# main.net
KiCad netlist of a schematic drawn in Altium Designer
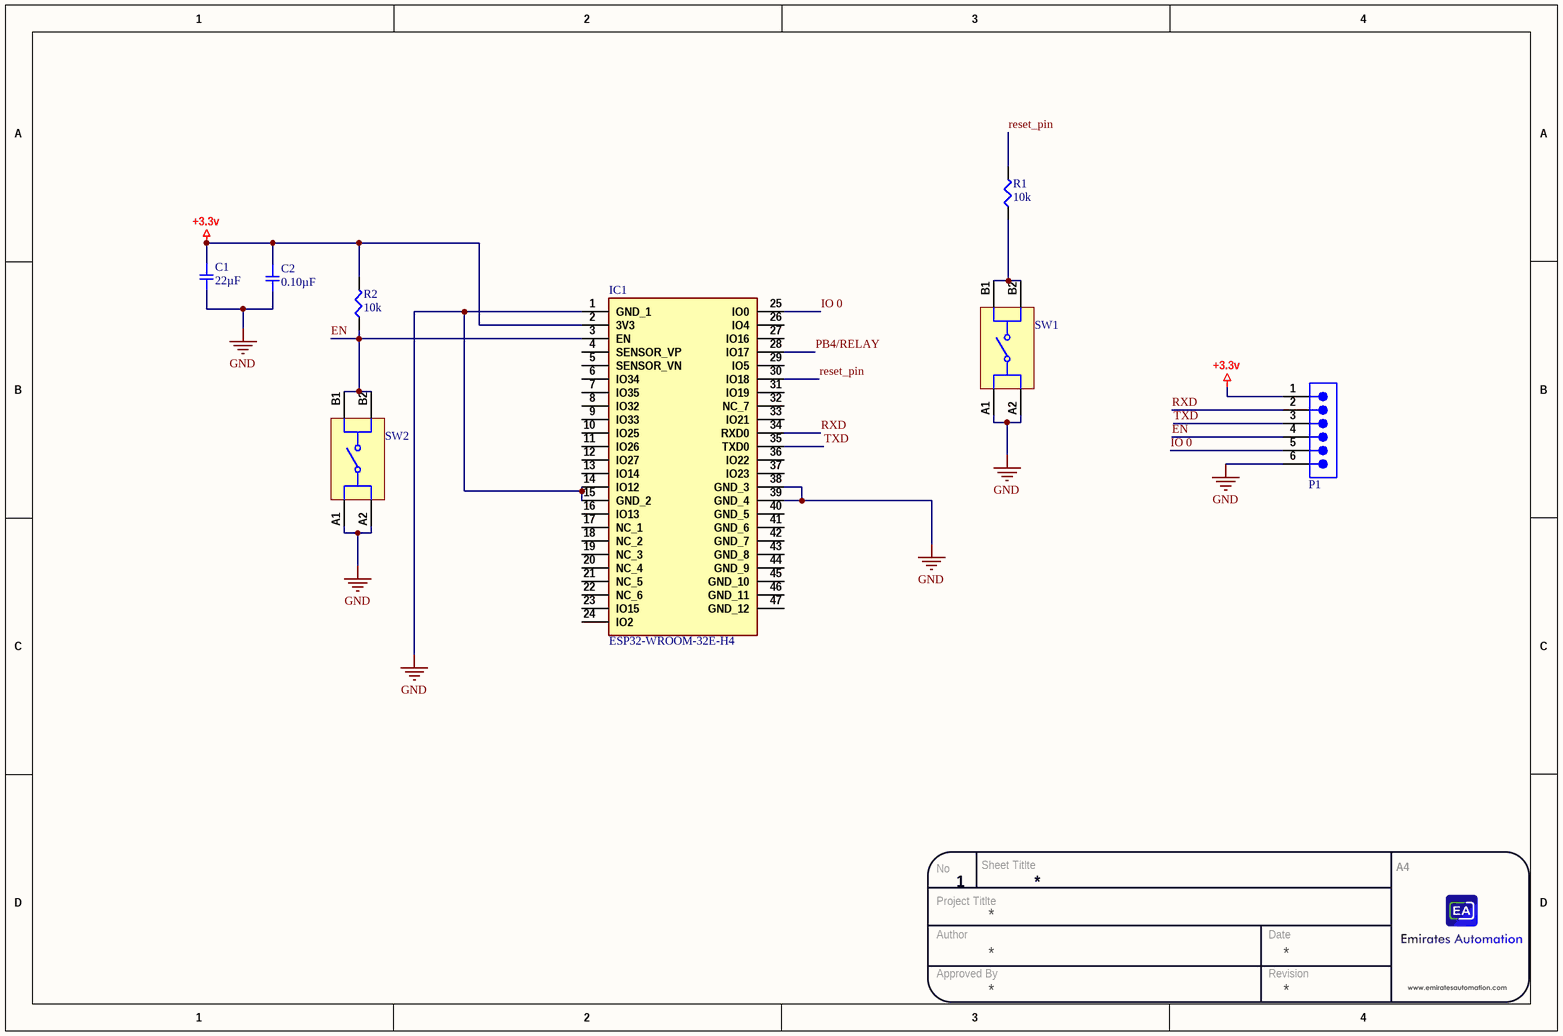
[diagram p0: main.SchDoc]

(export (version "E")
  (design (tool "Eeschema 10.0.6"))
  (components
    (comp (ref "C1")
      (value "22µF")
      (footprint "SMD-0603C")
      (description "CAP CER 22UF 10V X5R 0603")
      (fields
        (field (name "DIGI-KEY PART NUMBER") "490-10476-1-ND")
        (field (name "PART NUMBER") "GRM188R61A226ME15D")
      )
      (libsource (lib "capacitor_murata_0603") (part "GRM188R61A226ME15D"))
    )
    (comp (ref "C2")
      (value "0.10µF")
      (footprint "SMD-0603C")
      (description "CAP CER 0.1UF 16V X7R 0603")
      (fields
        (field (name "DIGI-KEY PART NUMBER") "490-5796-1-ND")
        (field (name "PART NUMBER") "GCJ188R71C104KA01D")
      )
      (libsource (lib "capacitor_murata_0603") (part "GCJ188R71C104KA01D"))
    )
    (comp (ref "IC1")
      (value "ESP32-WROOM-32E-H4")
      (footprint "SamacSys:ESP32WROOM32UEM113EH2800UH3Q0")
      (description "Integrated Circuit")
      (fields (field (name "MOUSER PART NUMBER") "356-ESP32WRM320EH3PS"))
      (libsource (lib "SamacSys") (part "ESP32-WROOM-32E-H4"))
    )
    (comp (ref "P1")
      (value "61300611121")
      (footprint "61300611121")
      (description "WR-PHD Pin Header, THT, Vertical, pitch 2.54mm, 1 Row, 6P")
      (fields (field (name "MANUFACTURER") "Wurth Elektronik"))
      (libsource (lib "Wurth_pin_header") (part "61300611121"))
    )
    (comp (ref "R1")
      (value "10k")
      (footprint "SMD-0603-RES")
      (description "RES SMD 10K OHM 1% 1/10W 0603")
      (fields
        (field (name "PART NUMBER") "ERJ-3EKF1002V")
        (field (name "DIGI-KEY PART NUMBER") "P10.0KHCT-ND")
      )
      (libsource (lib "Panasonic_ERJ_0603") (part "ERJ-3EKF1002V"))
    )
    (comp (ref "R2")
      (value "10k")
      (footprint "SMD-0603-RES")
      (description "RES SMD 10K OHM 1% 1/10W 0603")
      (fields
        (field (name "PART NUMBER") "ERJ-3EKF1002V")
        (field (name "DIGI-KEY PART NUMBER") "P10.0KHCT-ND")
      )
      (libsource (lib "Panasonic_ERJ_0603") (part "ERJ-3EKF1002V"))
    )
    (comp (ref "SW1")
      (value "430476085716")
      (footprint "430476085716")
      (description "WS-TATV THT Washable Tact Switch 12x12mm, 160g, SPST-NO, 12V, 50mA")
      (fields (field (name "MANUFACTURER") "Wurth Elektronik"))
      (libsource (lib "Wurth TATV THT Tact Switch 6x6 mm ") (part "430476085716"))
    )
    (comp (ref "SW2")
      (value "430476085716")
      (footprint "430476085716")
      (description "WS-TATV THT Washable Tact Switch 12x12mm, 160g, SPST-NO, 12V, 50mA")
      (fields (field (name "MANUFACTURER") "Wurth Elektronik"))
      (libsource (lib "Wurth TATV THT Tact Switch 6x6 mm ") (part "430476085716"))
    )
  )
  (nets
    (net (code "1") (name "+3.3v") (class "Default")
      (node (ref "C1") (pin "1") (pinfunction "1_1") (pintype "passive"))
      (node (ref "C2") (pin "1") (pinfunction "1_1") (pintype "passive"))
      (node (ref "IC1") (pin "2") (pinfunction "3V3_2") (pintype "passive"))
      (node (ref "P1") (pin "1") (pinfunction "1_1") (pintype "passive"))
      (node (ref "R2") (pin "2") (pinfunction "2_2") (pintype "passive"))
    )
    (net (code "2") (name "/EN") (class "Default")
      (node (ref "IC1") (pin "3") (pinfunction "EN_3") (pintype "passive"))
      (node (ref "P1") (pin "4") (pinfunction "4_4") (pintype "passive"))
      (node (ref "R2") (pin "1") (pinfunction "1_1") (pintype "passive"))
      (node (ref "SW2") (pin "B1") (pinfunction "B1_B1") (pintype "passive"))
      (node (ref "SW2") (pin "B2") (pinfunction "B2_B2") (pintype "passive"))
    )
    (net (code "3") (name "/IO 0") (class "Default")
      (node (ref "IC1") (pin "25") (pinfunction "IO0_25") (pintype "passive"))
      (node (ref "P1") (pin "5") (pinfunction "5_5") (pintype "passive"))
    )
    (net (code "4") (name "/PB4{slash}RELAY") (class "Default")
      (node (ref "IC1") (pin "28") (pinfunction "IO17_28") (pintype "passive"))
    )
    (net (code "5") (name "/RXD") (class "Default")
      (node (ref "IC1") (pin "34") (pinfunction "RXD0_34") (pintype "passive"))
      (node (ref "P1") (pin "2") (pinfunction "2_2") (pintype "passive"))
    )
    (net (code "6") (name "/TXD") (class "Default")
      (node (ref "IC1") (pin "35") (pinfunction "TXD0_35") (pintype "passive"))
      (node (ref "P1") (pin "3") (pinfunction "3_3") (pintype "passive"))
    )
    (net (code "7") (name "/reset_pin") (class "Default")
      (node (ref "IC1") (pin "30") (pinfunction "IO18_30") (pintype "passive"))
      (node (ref "R1") (pin "2") (pinfunction "2_2") (pintype "passive"))
    )
    (net (code "8") (name "GND") (class "Default")
      (node (ref "C1") (pin "2") (pinfunction "2_2") (pintype "passive"))
      (node (ref "C2") (pin "2") (pinfunction "2_2") (pintype "passive"))
      (node (ref "IC1") (pin "1") (pinfunction "GND_1_1") (pintype "passive"))
      (node (ref "IC1") (pin "14") (pinfunction "IO12_14") (pintype "passive"))
      (node (ref "IC1") (pin "15") (pinfunction "GND_2_15") (pintype "passive"))
      (node (ref "IC1") (pin "38") (pinfunction "GND_3_38") (pintype "passive"))
      (node (ref "IC1") (pin "39") (pinfunction "GND_4_39") (pintype "passive"))
      (node (ref "P1") (pin "6") (pinfunction "6_6") (pintype "passive"))
      (node (ref "SW1") (pin "A1") (pinfunction "A1_A1") (pintype "passive"))
      (node (ref "SW1") (pin "A2") (pinfunction "A2_A2") (pintype "passive"))
      (node (ref "SW2") (pin "A1") (pinfunction "A1_A1") (pintype "passive"))
      (node (ref "SW2") (pin "A2") (pinfunction "A2_A2") (pintype "passive"))
    )
    (net (code "9") (name "Net-(R1-Pad1)") (class "Default")
      (node (ref "R1") (pin "1") (pinfunction "1_1") (pintype "passive"))
      (node (ref "SW1") (pin "B1") (pinfunction "B1_B1") (pintype "passive"))
      (node (ref "SW1") (pin "B2") (pinfunction "B2_B2") (pintype "passive"))
    )
    (net (code "10") (name "unconnected-(IC1-GND_5-Pad40)") (class "Default")
      (node (ref "IC1") (pin "40") (pinfunction "GND_5_40") (pintype "passive"))
    )
    (net (code "11") (name "unconnected-(IC1-GND_6-Pad41)") (class "Default")
      (node (ref "IC1") (pin "41") (pinfunction "GND_6_41") (pintype "passive"))
    )
    (net (code "12") (name "unconnected-(IC1-GND_7-Pad42)") (class "Default")
      (node (ref "IC1") (pin "42") (pinfunction "GND_7_42") (pintype "passive"))
    )
    (net (code "13") (name "unconnected-(IC1-GND_8-Pad43)") (class "Default")
      (node (ref "IC1") (pin "43") (pinfunction "GND_8_43") (pintype "passive"))
    )
    (net (code "14") (name "unconnected-(IC1-GND_9-Pad44)") (class "Default")
      (node (ref "IC1") (pin "44") (pinfunction "GND_9_44") (pintype "passive"))
    )
    (net (code "15") (name "unconnected-(IC1-GND_10-Pad45)") (class "Default")
      (node (ref "IC1") (pin "45") (pinfunction "GND_10_45") (pintype "passive"))
    )
    (net (code "16") (name "unconnected-(IC1-GND_11-Pad46)") (class "Default")
      (node (ref "IC1") (pin "46") (pinfunction "GND_11_46") (pintype "passive"))
    )
    (net (code "17") (name "unconnected-(IC1-GND_12-Pad47)") (class "Default")
      (node (ref "IC1") (pin "47") (pinfunction "GND_12_47") (pintype "passive"))
    )
    (net (code "18") (name "unconnected-(IC1-IO2-Pad24)") (class "Default")
      (node (ref "IC1") (pin "24") (pinfunction "IO2_24") (pintype "passive"))
    )
    (net (code "19") (name "unconnected-(IC1-IO4-Pad26)") (class "Default")
      (node (ref "IC1") (pin "26") (pinfunction "IO4_26") (pintype "passive"))
    )
    (net (code "20") (name "unconnected-(IC1-IO5-Pad29)") (class "Default")
      (node (ref "IC1") (pin "29") (pinfunction "IO5_29") (pintype "passive"))
    )
    (net (code "21") (name "unconnected-(IC1-IO13-Pad16)") (class "Default")
      (node (ref "IC1") (pin "16") (pinfunction "IO13_16") (pintype "passive"))
    )
    (net (code "22") (name "unconnected-(IC1-IO14-Pad13)") (class "Default")
      (node (ref "IC1") (pin "13") (pinfunction "IO14_13") (pintype "passive"))
    )
    (net (code "23") (name "unconnected-(IC1-IO15-Pad23)") (class "Default")
      (node (ref "IC1") (pin "23") (pinfunction "IO15_23") (pintype "passive"))
    )
    (net (code "24") (name "unconnected-(IC1-IO16-Pad27)") (class "Default")
      (node (ref "IC1") (pin "27") (pinfunction "IO16_27") (pintype "passive"))
    )
    (net (code "25") (name "unconnected-(IC1-IO19-Pad31)") (class "Default")
      (node (ref "IC1") (pin "31") (pinfunction "IO19_31") (pintype "passive"))
    )
    (net (code "26") (name "unconnected-(IC1-IO21-Pad33)") (class "Default")
      (node (ref "IC1") (pin "33") (pinfunction "IO21_33") (pintype "passive"))
    )
    (net (code "27") (name "unconnected-(IC1-IO22-Pad36)") (class "Default")
      (node (ref "IC1") (pin "36") (pinfunction "IO22_36") (pintype "passive"))
    )
    (net (code "28") (name "unconnected-(IC1-IO23-Pad37)") (class "Default")
      (node (ref "IC1") (pin "37") (pinfunction "IO23_37") (pintype "passive"))
    )
    (net (code "29") (name "unconnected-(IC1-IO25-Pad10)") (class "Default")
      (node (ref "IC1") (pin "10") (pinfunction "IO25_10") (pintype "passive"))
    )
    (net (code "30") (name "unconnected-(IC1-IO26-Pad11)") (class "Default")
      (node (ref "IC1") (pin "11") (pinfunction "IO26_11") (pintype "passive"))
    )
    (net (code "31") (name "unconnected-(IC1-IO27-Pad12)") (class "Default")
      (node (ref "IC1") (pin "12") (pinfunction "IO27_12") (pintype "passive"))
    )
    (net (code "32") (name "unconnected-(IC1-IO32-Pad8)") (class "Default")
      (node (ref "IC1") (pin "8") (pinfunction "IO32_8") (pintype "passive"))
    )
    (net (code "33") (name "unconnected-(IC1-IO33-Pad9)") (class "Default")
      (node (ref "IC1") (pin "9") (pinfunction "IO33_9") (pintype "passive"))
    )
    (net (code "34") (name "unconnected-(IC1-IO34-Pad6)") (class "Default")
      (node (ref "IC1") (pin "6") (pinfunction "IO34_6") (pintype "passive"))
    )
    (net (code "35") (name "unconnected-(IC1-IO35-Pad7)") (class "Default")
      (node (ref "IC1") (pin "7") (pinfunction "IO35_7") (pintype "passive"))
    )
    (net (code "36") (name "unconnected-(IC1-NC_1-Pad17)") (class "Default")
      (node (ref "IC1") (pin "17") (pinfunction "NC_1_17") (pintype "passive"))
    )
    (net (code "37") (name "unconnected-(IC1-NC_2-Pad18)") (class "Default")
      (node (ref "IC1") (pin "18") (pinfunction "NC_2_18") (pintype "passive"))
    )
    (net (code "38") (name "unconnected-(IC1-NC_3-Pad19)") (class "Default")
      (node (ref "IC1") (pin "19") (pinfunction "NC_3_19") (pintype "passive"))
    )
    (net (code "39") (name "unconnected-(IC1-NC_4-Pad20)") (class "Default")
      (node (ref "IC1") (pin "20") (pinfunction "NC_4_20") (pintype "passive"))
    )
    (net (code "40") (name "unconnected-(IC1-NC_5-Pad21)") (class "Default")
      (node (ref "IC1") (pin "21") (pinfunction "NC_5_21") (pintype "passive"))
    )
    (net (code "41") (name "unconnected-(IC1-NC_6-Pad22)") (class "Default")
      (node (ref "IC1") (pin "22") (pinfunction "NC_6_22") (pintype "passive"))
    )
    (net (code "42") (name "unconnected-(IC1-NC_7-Pad32)") (class "Default")
      (node (ref "IC1") (pin "32") (pinfunction "NC_7_32") (pintype "passive"))
    )
    (net (code "43") (name "unconnected-(IC1-SENSOR_VN-Pad5)") (class "Default")
      (node (ref "IC1") (pin "5") (pinfunction "SENSOR_VN_5") (pintype "passive"))
    )
    (net (code "44") (name "unconnected-(IC1-SENSOR_VP-Pad4)") (class "Default")
      (node (ref "IC1") (pin "4") (pinfunction "SENSOR_VP_4") (pintype "passive"))
    )
  )
)
